# config-bank8.net
KiCad netlist of a schematic drawn in Altium Designer
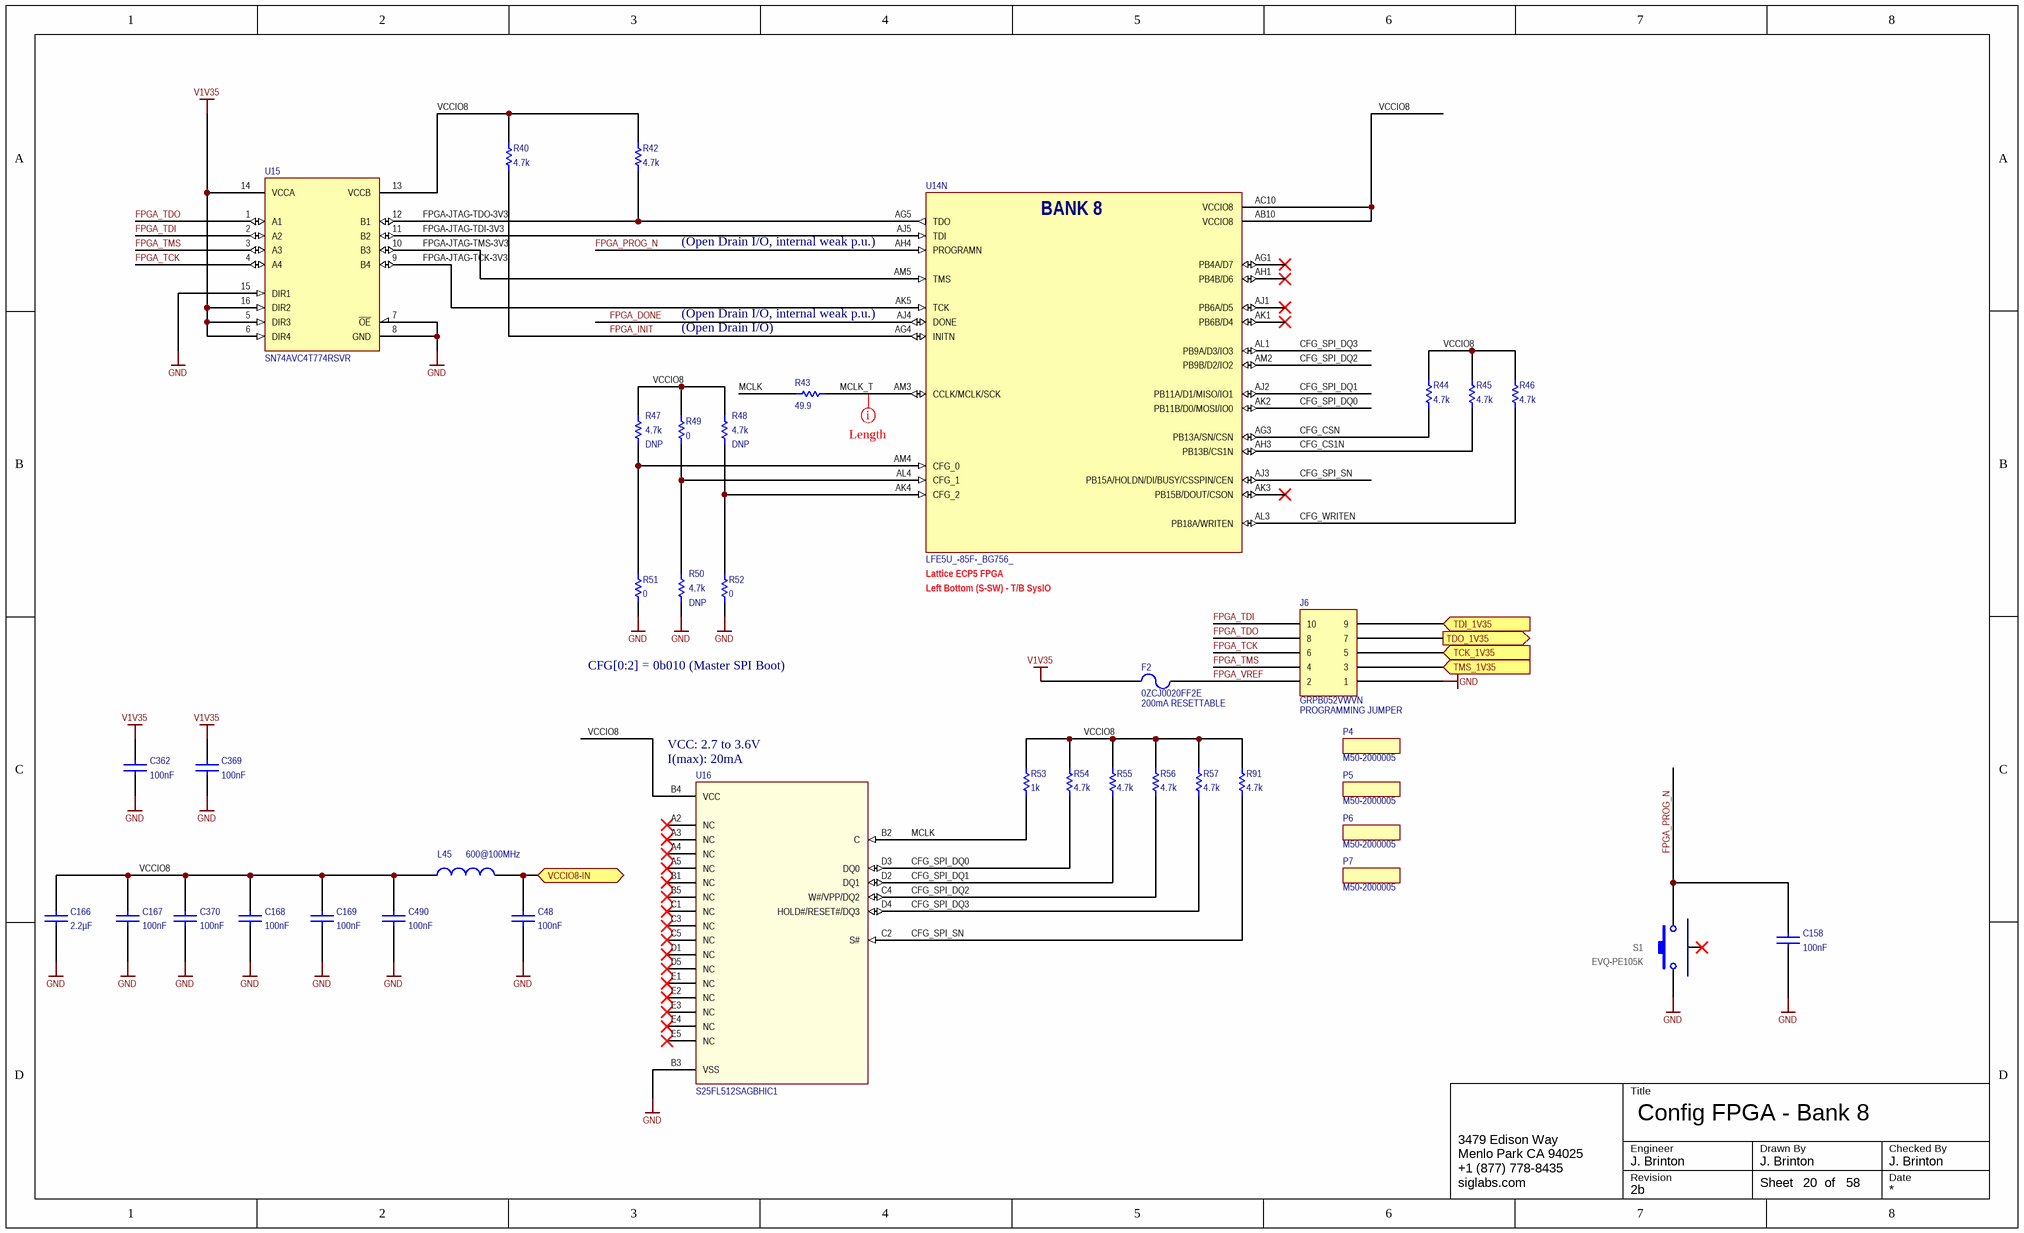
[diagram p0: config-bank8.SchDoc]

(export (version "E")
  (design (tool "Eeschema 10.0.6"))
  (components
    (comp (ref "C48")
      (value "100nF")
      (footprint "generic:CAPC1005X56N")
      (description "Ceramic Capacitor 100nF ±10% 16V X7R 0402")
      (fields (field (name "MANUFACTURER") "Murata") (field (name "TOLERANCE") "±10%"))
      (libsource (lib "murata") (part "GRM155R71A104KA01J"))
    )
    (comp (ref "C158")
      (value "100nF")
      (footprint "generic:CAPC1005X56N")
      (description "Ceramic Capacitor 100nF ±10% 16V X7R 0402")
      (fields (field (name "MANUFACTURER") "Murata") (field (name "TOLERANCE") "±10%"))
      (libsource (lib "murata") (part "GRM155R71A104KA01J"))
    )
    (comp (ref "C166")
      (value "2.2µF")
      (footprint "generic:CAPC1608X90N")
      (description "Ceramic Capacitor 2.2uF ±10% 10V X7R 0603")
      (fields (field (name "MANUFACTURER") "Murata") (field (name "TOLERANCE") "±10%"))
      (libsource (lib "murata") (part "GRM188R71A225KE15D"))
    )
    (comp (ref "C167")
      (value "100nF")
      (footprint "generic:CAPC1005X56N")
      (description "Ceramic Capacitor 100nF ±10% 16V X7R 0402")
      (fields (field (name "MANUFACTURER") "Murata") (field (name "TOLERANCE") "±10%"))
      (libsource (lib "murata") (part "GRM155R71A104KA01J"))
    )
    (comp (ref "C168")
      (value "100nF")
      (footprint "generic:CAPC1005X56N")
      (description "Ceramic Capacitor 100nF ±10% 16V X7R 0402")
      (fields (field (name "MANUFACTURER") "Murata") (field (name "TOLERANCE") "±10%"))
      (libsource (lib "murata") (part "GRM155R71A104KA01J"))
    )
    (comp (ref "C169")
      (value "100nF")
      (footprint "generic:CAPC1005X56N")
      (description "Ceramic Capacitor 100nF ±10% 16V X7R 0402")
      (fields (field (name "MANUFACTURER") "Murata") (field (name "TOLERANCE") "±10%"))
      (libsource (lib "murata") (part "GRM155R71A104KA01J"))
    )
    (comp (ref "C362")
      (value "100nF")
      (footprint "generic:CAPC1005X56N")
      (description "Ceramic Capacitor 100nF ±10% 16V X7R 0402")
      (fields (field (name "MANUFACTURER") "Murata") (field (name "TOLERANCE") "±10%"))
      (libsource (lib "murata") (part "GRM155R71A104KA01J"))
    )
    (comp (ref "C369")
      (value "100nF")
      (footprint "generic:CAPC1005X56N")
      (description "Ceramic Capacitor 100nF ±10% 16V X7R 0402")
      (fields (field (name "MANUFACTURER") "Murata") (field (name "TOLERANCE") "±10%"))
      (libsource (lib "murata") (part "GRM155R71A104KA01J"))
    )
    (comp (ref "C370")
      (value "100nF")
      (footprint "generic:CAPC1005X56N")
      (description "Ceramic Capacitor 100nF ±10% 16V X7R 0402")
      (fields (field (name "MANUFACTURER") "Murata") (field (name "TOLERANCE") "±10%"))
      (libsource (lib "murata") (part "GRM155R71A104KA01J"))
    )
    (comp (ref "C490")
      (value "100nF")
      (footprint "generic:CAPC1005X56N")
      (description "Ceramic Capacitor 100nF ±10% 16V X7R 0402")
      (fields (field (name "MANUFACTURER") "Murata") (field (name "TOLERANCE") "±10%"))
      (libsource (lib "murata") (part "GRM155R71A104KA01J"))
    )
    (comp (ref "F2")
      (value "0ZCJ0020FF2E")
      (footprint "generic:1206")
      (description "PTC Resettable Fuse, 0.2A, 30V, SMD 1206")
      (fields (field (name "MANUFACTURER") "Bell Fuse"))
      (libsource (lib "bel-fuse") (part "0ZCJ0020FF2E"))
    )
    (comp (ref "J6")
      (value "GRPB052VWVN")
      (footprint "sullins:GRPB052VWVN")
      (description "Male Header, 0.050\" Pitch, 2x5 Position")
      (fields (field (name "MANUFACTURER") "Sullins"))
      (libsource (lib "sullins") (part "GRPB052VWVN"))
    )
    (comp (ref "L45")
      (value "600@100MHz")
      (footprint "0402")
      (description "Ferrite Bead 600-Ohm @ 100MHz 900mA 0402")
      (fields (field (name "MANUFACTURER") "Murata") (field (name "TOLERANCE") "±25%"))
      (libsource (lib "Graviton") (part "IND 0402"))
    )
    (comp (ref "P4")
      (value "M50-2000005")
      (description "1.27mm Jumper Socket")
      (fields (field (name "MANUFACTURER") "Harwin"))
      (libsource (lib "harwin") (part "M50-1900005"))
    )
    (comp (ref "P5")
      (value "M50-2000005")
      (description "1.27mm Jumper Socket")
      (fields (field (name "MANUFACTURER") "Harwin"))
      (libsource (lib "harwin") (part "M50-1900005"))
    )
    (comp (ref "P6")
      (value "M50-2000005")
      (description "1.27mm Jumper Socket")
      (fields (field (name "MANUFACTURER") "Harwin"))
      (libsource (lib "harwin") (part "M50-1900005"))
    )
    (comp (ref "P7")
      (value "M50-2000005")
      (description "1.27mm Jumper Socket")
      (fields (field (name "MANUFACTURER") "Harwin"))
      (libsource (lib "harwin") (part "M50-1900005"))
    )
    (comp (ref "R40")
      (value "4.7k")
      (footprint "generic:0603")
      (description "Thick Film Resistor 4.7k ±1% 0603")
      (fields (field (name "TOLERANCE") "±1%") (field (name "MANUFACTURER") "Panasonic"))
      (libsource (lib "brinton") (part "RES"))
    )
    (comp (ref "R42")
      (value "4.7k")
      (footprint "generic:0603")
      (description "Thick Film Resistor 4.7k ±1% 0603")
      (fields (field (name "TOLERANCE") "±1%") (field (name "MANUFACTURER") "Panasonic"))
      (libsource (lib "brinton") (part "RES"))
    )
    (comp (ref "R43")
      (value "49.9")
      (footprint "generic:0603")
      (description "Thick Film Resistor 49.9 ±1% 0603")
      (fields (field (name "TOLERANCE") "±1%") (field (name "MANUFACTURER") "Panasonic"))
      (libsource (lib "brinton") (part "RES"))
    )
    (comp (ref "R44")
      (value "4.7k")
      (footprint "generic:0603")
      (description "Thick Film Resistor 4.7k ±1% 0603")
      (fields (field (name "TOLERANCE") "±1%") (field (name "MANUFACTURER") "Panasonic"))
      (libsource (lib "brinton") (part "RES"))
    )
    (comp (ref "R45")
      (value "4.7k")
      (footprint "generic:0603")
      (description "Thick Film Resistor 4.7k ±1% 0603")
      (fields (field (name "TOLERANCE") "±1%") (field (name "MANUFACTURER") "Panasonic"))
      (libsource (lib "brinton") (part "RES"))
    )
    (comp (ref "R46")
      (value "4.7k")
      (footprint "generic:0603")
      (description "Thick Film Resistor 4.7k ±1% 0603")
      (fields (field (name "TOLERANCE") "±1%") (field (name "MANUFACTURER") "Panasonic"))
      (libsource (lib "brinton") (part "RES"))
    )
    (comp (ref "R47")
      (value "4.7k")
      (footprint "generic:0603")
      (description "Thick Film Resistor 4.7k ±1% 0603")
      (fields
        (field (name "TOLERANCE") "±1%")
        (field (name "MANUFACTURER") "Panasonic")
        (field (name "DO NOT PLACE") "DNP")
      )
      (libsource (lib "brinton") (part "RES"))
    )
    (comp (ref "R48")
      (value "4.7k")
      (footprint "generic:0603")
      (description "Thick Film Resistor 4.7k ±1% 0603")
      (fields
        (field (name "TOLERANCE") "±1%")
        (field (name "MANUFACTURER") "Panasonic")
        (field (name "DO NOT PLACE") "DNP")
      )
      (libsource (lib "brinton") (part "RES"))
    )
    (comp (ref "R49")
      (value "0")
      (footprint "generic:0603")
      (description "Thick Film Resistor Jumper 0603")
      (fields (field (name "MANUFACTURER") "Panasonic") (field (name "Comment") "ERJ-3GEY0R00V"))
      (libsource (lib "brinton") (part "RES"))
    )
    (comp (ref "R50")
      (value "4.7k")
      (footprint "generic:0603")
      (description "Thick Film Resistor 4.7k ±1% 0603")
      (fields
        (field (name "TOLERANCE") "±1%")
        (field (name "MANUFACTURER") "Panasonic")
        (field (name "DO NOT PLACE") "DNP")
      )
      (libsource (lib "brinton") (part "RES"))
    )
    (comp (ref "R51")
      (value "0")
      (footprint "generic:0603")
      (description "Thick Film Resistor Jumper 0603")
      (fields (field (name "MANUFACTURER") "Panasonic") (field (name "Comment") "ERJ-3GEY0R00V"))
      (libsource (lib "brinton") (part "RES"))
    )
    (comp (ref "R52")
      (value "0")
      (footprint "generic:0603")
      (description "Thick Film Resistor Jumper 0603")
      (fields (field (name "MANUFACTURER") "Panasonic") (field (name "Comment") "ERJ-3GEY0R00V"))
      (libsource (lib "brinton") (part "RES"))
    )
    (comp (ref "R53")
      (value "1k")
      (footprint "0402")
      (description "Thick Film Resistor 1k ±1% 0402")
      (fields (field (name "TOLERANCE") "±1%") (field (name "MANUFACTURER") "Yageo"))
      (libsource (lib "brinton") (part "RES"))
    )
    (comp (ref "R54")
      (value "4.7k")
      (footprint "generic:0603")
      (description "Thick Film Resistor 4.7k ±1% 0603")
      (fields (field (name "TOLERANCE") "±1%") (field (name "MANUFACTURER") "Panasonic"))
      (libsource (lib "brinton") (part "RES"))
    )
    (comp (ref "R55")
      (value "4.7k")
      (footprint "generic:0603")
      (description "Thick Film Resistor 4.7k ±1% 0603")
      (fields (field (name "TOLERANCE") "±1%") (field (name "MANUFACTURER") "Panasonic"))
      (libsource (lib "brinton") (part "RES"))
    )
    (comp (ref "R56")
      (value "4.7k")
      (footprint "generic:0603")
      (description "Thick Film Resistor 4.7k ±1% 0603")
      (fields (field (name "TOLERANCE") "±1%") (field (name "MANUFACTURER") "Panasonic"))
      (libsource (lib "brinton") (part "RES"))
    )
    (comp (ref "R57")
      (value "4.7k")
      (footprint "generic:0603")
      (description "Thick Film Resistor 4.7k ±1% 0603")
      (fields (field (name "TOLERANCE") "±1%") (field (name "MANUFACTURER") "Panasonic"))
      (libsource (lib "brinton") (part "RES"))
    )
    (comp (ref "R91")
      (value "4.7k")
      (footprint "generic:0603")
      (description "Thick Film Resistor 4.7k ±1% 0603")
      (fields (field (name "TOLERANCE") "±1%") (field (name "MANUFACTURER") "Panasonic"))
      (libsource (lib "brinton") (part "RES"))
    )
    (comp (ref "S1")
      (value "EVQ-PE105K")
      (footprint "EVQ-PE105K")
      (description "Tactile Switch; Normally Open")
      (fields (field (name "MANUFACTURER") "Panasonic"))
      (libsource (lib "panasonic") (part "EVQ-PF006K"))
    )
    (comp (ref "U14")
      (value "LFE5U_-85F-_BG756_")
      (footprint "lattice:caBGA756")
      (description "ECP5 FPGA, 85k LUT, 756-caBGA")
      (fields (field (name "MANUFACTURER") "Lattice Semiconductor"))
      (libsource (lib "lattice") (part "LFE5U_-85F-_BG756_"))
    )
    (comp (ref "U15")
      (value "SN74AVC4T774RSVR")
      (footprint "RSV")
      (description "4-Bit Dual-Supply Bus Transceiver")
      (fields (field (name "MANUFACTURER") "Texas Instruments"))
      (libsource (lib "ti") (part "SN74AVC4T774RSVR"))
    )
    (comp (ref "U16")
      (value "S25FL512SAGBHIC1")
      (description "1024Mb, 3.3V Serial Flash Memory LBGA24")
      (fields (field (name "MANUFACTURER") "Cypress"))
      (libsource (lib "micron") (part "N25Q00AA13G1240"))
    )
  )
  (nets
    (net (code "1") (name "/CFG_CS1N") (class "Default")
      (node (ref "R45") (pin "1") (pinfunction "1_1") (pintype "passive"))
      (node (ref "U14") (pin "AH3") (pinfunction "PB13B/CS1N_AH3") (pintype "bidirectional"))
    )
    (net (code "2") (name "/CFG_CSN") (class "Default")
      (node (ref "R44") (pin "1") (pinfunction "1_1") (pintype "passive"))
      (node (ref "U14") (pin "AG3") (pinfunction "PB13A/SN/CSN_AG3") (pintype "bidirectional"))
    )
    (net (code "3") (name "/CFG_SPI_DQ0") (class "Default")
      (node (ref "R54") (pin "1") (pinfunction "1_1") (pintype "passive"))
      (node (ref "U14") (pin "AK2") (pinfunction "PB11B/D0/MOSI/IO0_AK2") (pintype "bidirectional"))
      (node (ref "U16") (pin "D3") (pinfunction "DQ0_D3") (pintype "bidirectional"))
    )
    (net (code "4") (name "/CFG_SPI_DQ1") (class "Default")
      (node (ref "R55") (pin "1") (pinfunction "1_1") (pintype "passive"))
      (node (ref "U14") (pin "AJ2") (pinfunction "PB11A/D1/MISO/IO1_AJ2") (pintype "bidirectional"))
      (node (ref "U16") (pin "D2") (pinfunction "DQ1_D2") (pintype "bidirectional"))
    )
    (net (code "5") (name "/CFG_SPI_DQ2") (class "Default")
      (node (ref "R56") (pin "1") (pinfunction "1_1") (pintype "passive"))
      (node (ref "U14") (pin "AM2") (pinfunction "PB9B/D2/IO2_AM2") (pintype "bidirectional"))
      (node (ref "U16") (pin "C4") (pinfunction "W#/VPP/DQ2_C4") (pintype "bidirectional"))
    )
    (net (code "6") (name "/CFG_SPI_DQ3") (class "Default")
      (node (ref "R57") (pin "1") (pinfunction "1_1") (pintype "passive"))
      (node (ref "U14") (pin "AL1") (pinfunction "PB9A/D3/IO3_AL1") (pintype "bidirectional"))
      (node (ref "U16") (pin "D4") (pinfunction "HOLD#/RESET#/DQ3_D4") (pintype "bidirectional"))
    )
    (net (code "7") (name "/CFG_SPI_SN") (class "Default")
      (node (ref "R91") (pin "1") (pinfunction "1_1") (pintype "passive"))
      (node (ref "U14") (pin "AJ3") (pinfunction "PB15A/HOLDN/DI/BUSY/CSSPIN/CEN_AJ3") (pintype "bidirectional"))
      (node (ref "U16") (pin "C2") (pinfunction "S#_C2") (pintype "input"))
    )
    (net (code "8") (name "/CFG_WRITEN") (class "Default")
      (node (ref "R46") (pin "1") (pinfunction "1_1") (pintype "passive"))
      (node (ref "U14") (pin "AL3") (pinfunction "PB18A/WRITEN_AL3") (pintype "bidirectional"))
    )
    (net (code "9") (name "/FPGA-JTAG-TCK-3V3") (class "Default")
      (node (ref "U14") (pin "AK5") (pinfunction "TCK_AK5") (pintype "input"))
      (node (ref "U15") (pin "9") (pinfunction "B4_9") (pintype "bidirectional"))
    )
    (net (code "10") (name "/FPGA-JTAG-TDI-3V3") (class "Default")
      (node (ref "U14") (pin "AJ5") (pinfunction "TDI_AJ5") (pintype "input"))
      (node (ref "U15") (pin "11") (pinfunction "B2_11") (pintype "bidirectional"))
    )
    (net (code "11") (name "/FPGA-JTAG-TDO-3V3") (class "Default")
      (node (ref "R42") (pin "1") (pinfunction "1_1") (pintype "passive"))
      (node (ref "U14") (pin "AG5") (pinfunction "TDO_AG5") (pintype "output"))
      (node (ref "U15") (pin "12") (pinfunction "B1_12") (pintype "bidirectional"))
    )
    (net (code "12") (name "/FPGA-JTAG-TMS-3V3") (class "Default")
      (node (ref "U14") (pin "AM5") (pinfunction "TMS_AM5") (pintype "input"))
      (node (ref "U15") (pin "10") (pinfunction "B3_10") (pintype "bidirectional"))
    )
    (net (code "13") (name "/FPGA_DONE") (class "Default")
      (node (ref "U14") (pin "AJ4") (pinfunction "DONE_AJ4") (pintype "bidirectional"))
    )
    (net (code "14") (name "/FPGA_INIT") (class "Default")
      (node (ref "R40") (pin "1") (pinfunction "1_1") (pintype "passive"))
      (node (ref "U14") (pin "AG4") (pinfunction "INITN_AG4") (pintype "bidirectional"))
    )
    (net (code "15") (name "/FPGA_PROG_N") (class "Default")
      (node (ref "C158") (pin "2") (pinfunction "2_2") (pintype "passive"))
      (node (ref "S1") (pin "2") (pinfunction "2_2") (pintype "passive"))
      (node (ref "U14") (pin "AH4") (pinfunction "PROGRAMN_AH4") (pintype "input"))
    )
    (net (code "16") (name "/FPGA_TCK") (class "Default")
      (node (ref "J6") (pin "6") (pinfunction "6_6") (pintype "passive"))
      (node (ref "U15") (pin "4") (pinfunction "A4_4") (pintype "bidirectional"))
    )
    (net (code "17") (name "/FPGA_TDI") (class "Default")
      (node (ref "J6") (pin "10") (pinfunction "10_10") (pintype "passive"))
      (node (ref "U15") (pin "2") (pinfunction "A2_2") (pintype "bidirectional"))
    )
    (net (code "18") (name "/FPGA_TDO") (class "Default")
      (node (ref "J6") (pin "8") (pinfunction "8_8") (pintype "passive"))
      (node (ref "U15") (pin "1") (pinfunction "A1_1") (pintype "bidirectional"))
    )
    (net (code "19") (name "/FPGA_TMS") (class "Default")
      (node (ref "J6") (pin "4") (pinfunction "4_4") (pintype "passive"))
      (node (ref "U15") (pin "3") (pinfunction "A3_3") (pintype "bidirectional"))
    )
    (net (code "20") (name "/FPGA_VREF") (class "Default")
      (node (ref "F2") (pin "2") (pinfunction "2_2") (pintype "passive"))
      (node (ref "J6") (pin "2") (pinfunction "2_2") (pintype "passive"))
    )
    (net (code "21") (name "/MCLK") (class "Default")
      (node (ref "R43") (pin "2") (pinfunction "2_2") (pintype "passive"))
      (node (ref "R53") (pin "1") (pinfunction "1_1") (pintype "passive"))
      (node (ref "U16") (pin "B2") (pinfunction "C_B2") (pintype "input"))
    )
    (net (code "22") (name "/MCLK_T") (class "Default")
      (node (ref "R43") (pin "1") (pinfunction "1_1") (pintype "passive"))
      (node (ref "U14") (pin "AM3") (pinfunction "CCLK/MCLK/SCK_AM3") (pintype "bidirectional"))
    )
    (net (code "23") (name "/TCK_1V35") (class "Default")
      (node (ref "J6") (pin "5") (pinfunction "5_5") (pintype "passive"))
    )
    (net (code "24") (name "/TDI_1V35") (class "Default")
      (node (ref "J6") (pin "9") (pinfunction "9_9") (pintype "passive"))
    )
    (net (code "25") (name "/TDO_1V35") (class "Default")
      (node (ref "J6") (pin "7") (pinfunction "7_7") (pintype "passive"))
    )
    (net (code "26") (name "/TMS_1V35") (class "Default")
      (node (ref "J6") (pin "3") (pinfunction "3_3") (pintype "passive"))
    )
    (net (code "27") (name "/VCCIO8") (class "Default")
      (node (ref "C166") (pin "2") (pinfunction "2_2") (pintype "passive"))
      (node (ref "C167") (pin "2") (pinfunction "2_2") (pintype "passive"))
      (node (ref "C168") (pin "2") (pinfunction "2_2") (pintype "passive"))
      (node (ref "C169") (pin "2") (pinfunction "2_2") (pintype "passive"))
      (node (ref "C370") (pin "2") (pinfunction "2_2") (pintype "passive"))
      (node (ref "C490") (pin "2") (pinfunction "2_2") (pintype "passive"))
      (node (ref "L45") (pin "2") (pinfunction "2_2") (pintype "passive"))
      (node (ref "R40") (pin "2") (pinfunction "2_2") (pintype "passive"))
      (node (ref "R42") (pin "2") (pinfunction "2_2") (pintype "passive"))
      (node (ref "R44") (pin "2") (pinfunction "2_2") (pintype "passive"))
      (node (ref "R45") (pin "2") (pinfunction "2_2") (pintype "passive"))
      (node (ref "R46") (pin "2") (pinfunction "2_2") (pintype "passive"))
      (node (ref "R47") (pin "2") (pinfunction "2_2") (pintype "passive"))
      (node (ref "R48") (pin "2") (pinfunction "2_2") (pintype "passive"))
      (node (ref "R49") (pin "2") (pinfunction "2_2") (pintype "passive"))
      (node (ref "R53") (pin "2") (pinfunction "2_2") (pintype "passive"))
      (node (ref "R54") (pin "2") (pinfunction "2_2") (pintype "passive"))
      (node (ref "R55") (pin "2") (pinfunction "2_2") (pintype "passive"))
      (node (ref "R56") (pin "2") (pinfunction "2_2") (pintype "passive"))
      (node (ref "R57") (pin "2") (pinfunction "2_2") (pintype "passive"))
      (node (ref "R91") (pin "2") (pinfunction "2_2") (pintype "passive"))
      (node (ref "U14") (pin "AB10") (pinfunction "VCCIO8_AB10") (pintype "power_in"))
      (node (ref "U14") (pin "AC10") (pinfunction "VCCIO8_AC10") (pintype "power_in"))
      (node (ref "U15") (pin "13") (pinfunction "VCCB_13") (pintype "power_in"))
      (node (ref "U16") (pin "B4") (pinfunction "VCC_B4") (pintype "power_in"))
    )
    (net (code "28") (name "/VCCIO8-IN") (class "Default")
      (node (ref "C48") (pin "2") (pinfunction "2_2") (pintype "passive"))
      (node (ref "L45") (pin "1") (pinfunction "1_1") (pintype "passive"))
    )
    (net (code "29") (name "GND") (class "Default")
      (node (ref "C158") (pin "1") (pinfunction "1_1") (pintype "passive"))
      (node (ref "C166") (pin "1") (pinfunction "1_1") (pintype "passive"))
      (node (ref "C167") (pin "1") (pinfunction "1_1") (pintype "passive"))
      (node (ref "C168") (pin "1") (pinfunction "1_1") (pintype "passive"))
      (node (ref "C169") (pin "1") (pinfunction "1_1") (pintype "passive"))
      (node (ref "C362") (pin "1") (pinfunction "1_1") (pintype "passive"))
      (node (ref "C369") (pin "1") (pinfunction "1_1") (pintype "passive"))
      (node (ref "C370") (pin "1") (pinfunction "1_1") (pintype "passive"))
      (node (ref "C48") (pin "1") (pinfunction "1_1") (pintype "passive"))
      (node (ref "C490") (pin "1") (pinfunction "1_1") (pintype "passive"))
      (node (ref "J6") (pin "1") (pinfunction "1_1") (pintype "passive"))
      (node (ref "R50") (pin "1") (pinfunction "1_1") (pintype "passive"))
      (node (ref "R51") (pin "1") (pinfunction "1_1") (pintype "passive"))
      (node (ref "R52") (pin "1") (pinfunction "1_1") (pintype "passive"))
      (node (ref "S1") (pin "1") (pinfunction "1_1") (pintype "passive"))
      (node (ref "U15") (pin "15") (pinfunction "DIR1_15") (pintype "input"))
      (node (ref "U15") (pin "7") (pinfunction "OE_7") (pintype "passive"))
      (node (ref "U15") (pin "8") (pinfunction "GND_8") (pintype "power_in"))
      (node (ref "U16") (pin "B3") (pinfunction "VSS_B3") (pintype "power_in"))
    )
    (net (code "30") (name "Net-(U14N-CFG_0)") (class "Default")
      (node (ref "R47") (pin "1") (pinfunction "1_1") (pintype "passive"))
      (node (ref "R51") (pin "2") (pinfunction "2_2") (pintype "passive"))
      (node (ref "U14") (pin "AM4") (pinfunction "CFG_0_AM4") (pintype "input"))
    )
    (net (code "31") (name "Net-(U14N-CFG_1)") (class "Default")
      (node (ref "R49") (pin "1") (pinfunction "1_1") (pintype "passive"))
      (node (ref "R50") (pin "2") (pinfunction "2_2") (pintype "passive"))
      (node (ref "U14") (pin "AL4") (pinfunction "CFG_1_AL4") (pintype "input"))
    )
    (net (code "32") (name "Net-(U14N-CFG_2)") (class "Default")
      (node (ref "R48") (pin "1") (pinfunction "1_1") (pintype "passive"))
      (node (ref "R52") (pin "2") (pinfunction "2_2") (pintype "passive"))
      (node (ref "U14") (pin "AK4") (pinfunction "CFG_2_AK4") (pintype "input"))
    )
    (net (code "33") (name "V1V35") (class "Default")
      (node (ref "C362") (pin "2") (pinfunction "2_2") (pintype "passive"))
      (node (ref "C369") (pin "2") (pinfunction "2_2") (pintype "passive"))
      (node (ref "F2") (pin "1") (pinfunction "1_1") (pintype "passive"))
      (node (ref "U15") (pin "14") (pinfunction "VCCA_14") (pintype "power_in"))
      (node (ref "U15") (pin "16") (pinfunction "DIR2_16") (pintype "input"))
      (node (ref "U15") (pin "5") (pinfunction "DIR3_5") (pintype "input"))
      (node (ref "U15") (pin "6") (pinfunction "DIR4_6") (pintype "input"))
    )
    (net (code "34") (name "unconnected-(S1-Pad3)") (class "Default")
      (node (ref "S1") (pin "3") (pinfunction "3_3") (pintype "passive+no_connect"))
    )
    (net (code "35") (name "unconnected-(U14N-PB4A{slash}D7-PadAG1)") (class "Default")
      (node (ref "U14") (pin "AG1") (pinfunction "PB4A/D7_AG1") (pintype "bidirectional+no_connect"))
    )
    (net (code "36") (name "unconnected-(U14N-PB4B{slash}D6-PadAH1)") (class "Default")
      (node (ref "U14") (pin "AH1") (pinfunction "PB4B/D6_AH1") (pintype "bidirectional+no_connect"))
    )
    (net (code "37") (name "unconnected-(U14N-PB6A{slash}D5-PadAJ1)") (class "Default")
      (node (ref "U14") (pin "AJ1") (pinfunction "PB6A/D5_AJ1") (pintype "bidirectional+no_connect"))
    )
    (net (code "38") (name "unconnected-(U14N-PB6B{slash}D4-PadAK1)") (class "Default")
      (node (ref "U14") (pin "AK1") (pinfunction "PB6B/D4_AK1") (pintype "bidirectional+no_connect"))
    )
    (net (code "39") (name "unconnected-(U14N-PB15B{slash}DOUT{slash}CSON-PadAK3)") (class "Default")
      (node (ref "U14") (pin "AK3") (pinfunction "PB15B/DOUT/CSON_AK3") (pintype "bidirectional+no_connect"))
    )
    (net (code "40") (name "unconnected-(U16-NC-PadA2)") (class "Default")
      (node (ref "U16") (pin "A2") (pinfunction "NC_A2") (pintype "passive+no_connect"))
    )
    (net (code "41") (name "unconnected-(U16-NC-PadA3)") (class "Default")
      (node (ref "U16") (pin "A3") (pinfunction "NC_A3") (pintype "passive+no_connect"))
    )
    (net (code "42") (name "unconnected-(U16-NC-PadA4)") (class "Default")
      (node (ref "U16") (pin "A4") (pinfunction "NC_A4") (pintype "passive+no_connect"))
    )
    (net (code "43") (name "unconnected-(U16-NC-PadA5)") (class "Default")
      (node (ref "U16") (pin "A5") (pinfunction "NC_A5") (pintype "passive+no_connect"))
    )
    (net (code "44") (name "unconnected-(U16-NC-PadB1)") (class "Default")
      (node (ref "U16") (pin "B1") (pinfunction "NC_B1") (pintype "passive+no_connect"))
    )
    (net (code "45") (name "unconnected-(U16-NC-PadB5)") (class "Default")
      (node (ref "U16") (pin "B5") (pinfunction "NC_B5") (pintype "passive+no_connect"))
    )
    (net (code "46") (name "unconnected-(U16-NC-PadC1)") (class "Default")
      (node (ref "U16") (pin "C1") (pinfunction "NC_C1") (pintype "passive+no_connect"))
    )
    (net (code "47") (name "unconnected-(U16-NC-PadC3)") (class "Default")
      (node (ref "U16") (pin "C3") (pinfunction "NC_C3") (pintype "passive+no_connect"))
    )
    (net (code "48") (name "unconnected-(U16-NC-PadC5)") (class "Default")
      (node (ref "U16") (pin "C5") (pinfunction "NC_C5") (pintype "passive+no_connect"))
    )
    (net (code "49") (name "unconnected-(U16-NC-PadD1)") (class "Default")
      (node (ref "U16") (pin "D1") (pinfunction "NC_D1") (pintype "passive+no_connect"))
    )
    (net (code "50") (name "unconnected-(U16-NC-PadD5)") (class "Default")
      (node (ref "U16") (pin "D5") (pinfunction "NC_D5") (pintype "passive+no_connect"))
    )
    (net (code "51") (name "unconnected-(U16-NC-PadE1)") (class "Default")
      (node (ref "U16") (pin "E1") (pinfunction "NC_E1") (pintype "passive+no_connect"))
    )
    (net (code "52") (name "unconnected-(U16-NC-PadE2)") (class "Default")
      (node (ref "U16") (pin "E2") (pinfunction "NC_E2") (pintype "passive+no_connect"))
    )
    (net (code "53") (name "unconnected-(U16-NC-PadE3)") (class "Default")
      (node (ref "U16") (pin "E3") (pinfunction "NC_E3") (pintype "passive+no_connect"))
    )
    (net (code "54") (name "unconnected-(U16-NC-PadE4)") (class "Default")
      (node (ref "U16") (pin "E4") (pinfunction "NC_E4") (pintype "passive+no_connect"))
    )
    (net (code "55") (name "unconnected-(U16-NC-PadE5)") (class "Default")
      (node (ref "U16") (pin "E5") (pinfunction "NC_E5") (pintype "passive+no_connect"))
    )
  )
)
